# Jafar-SE_-_EasyEDA_-_Schematic_Export.net
KiCad netlist of a schematic drawn in EasyEDA
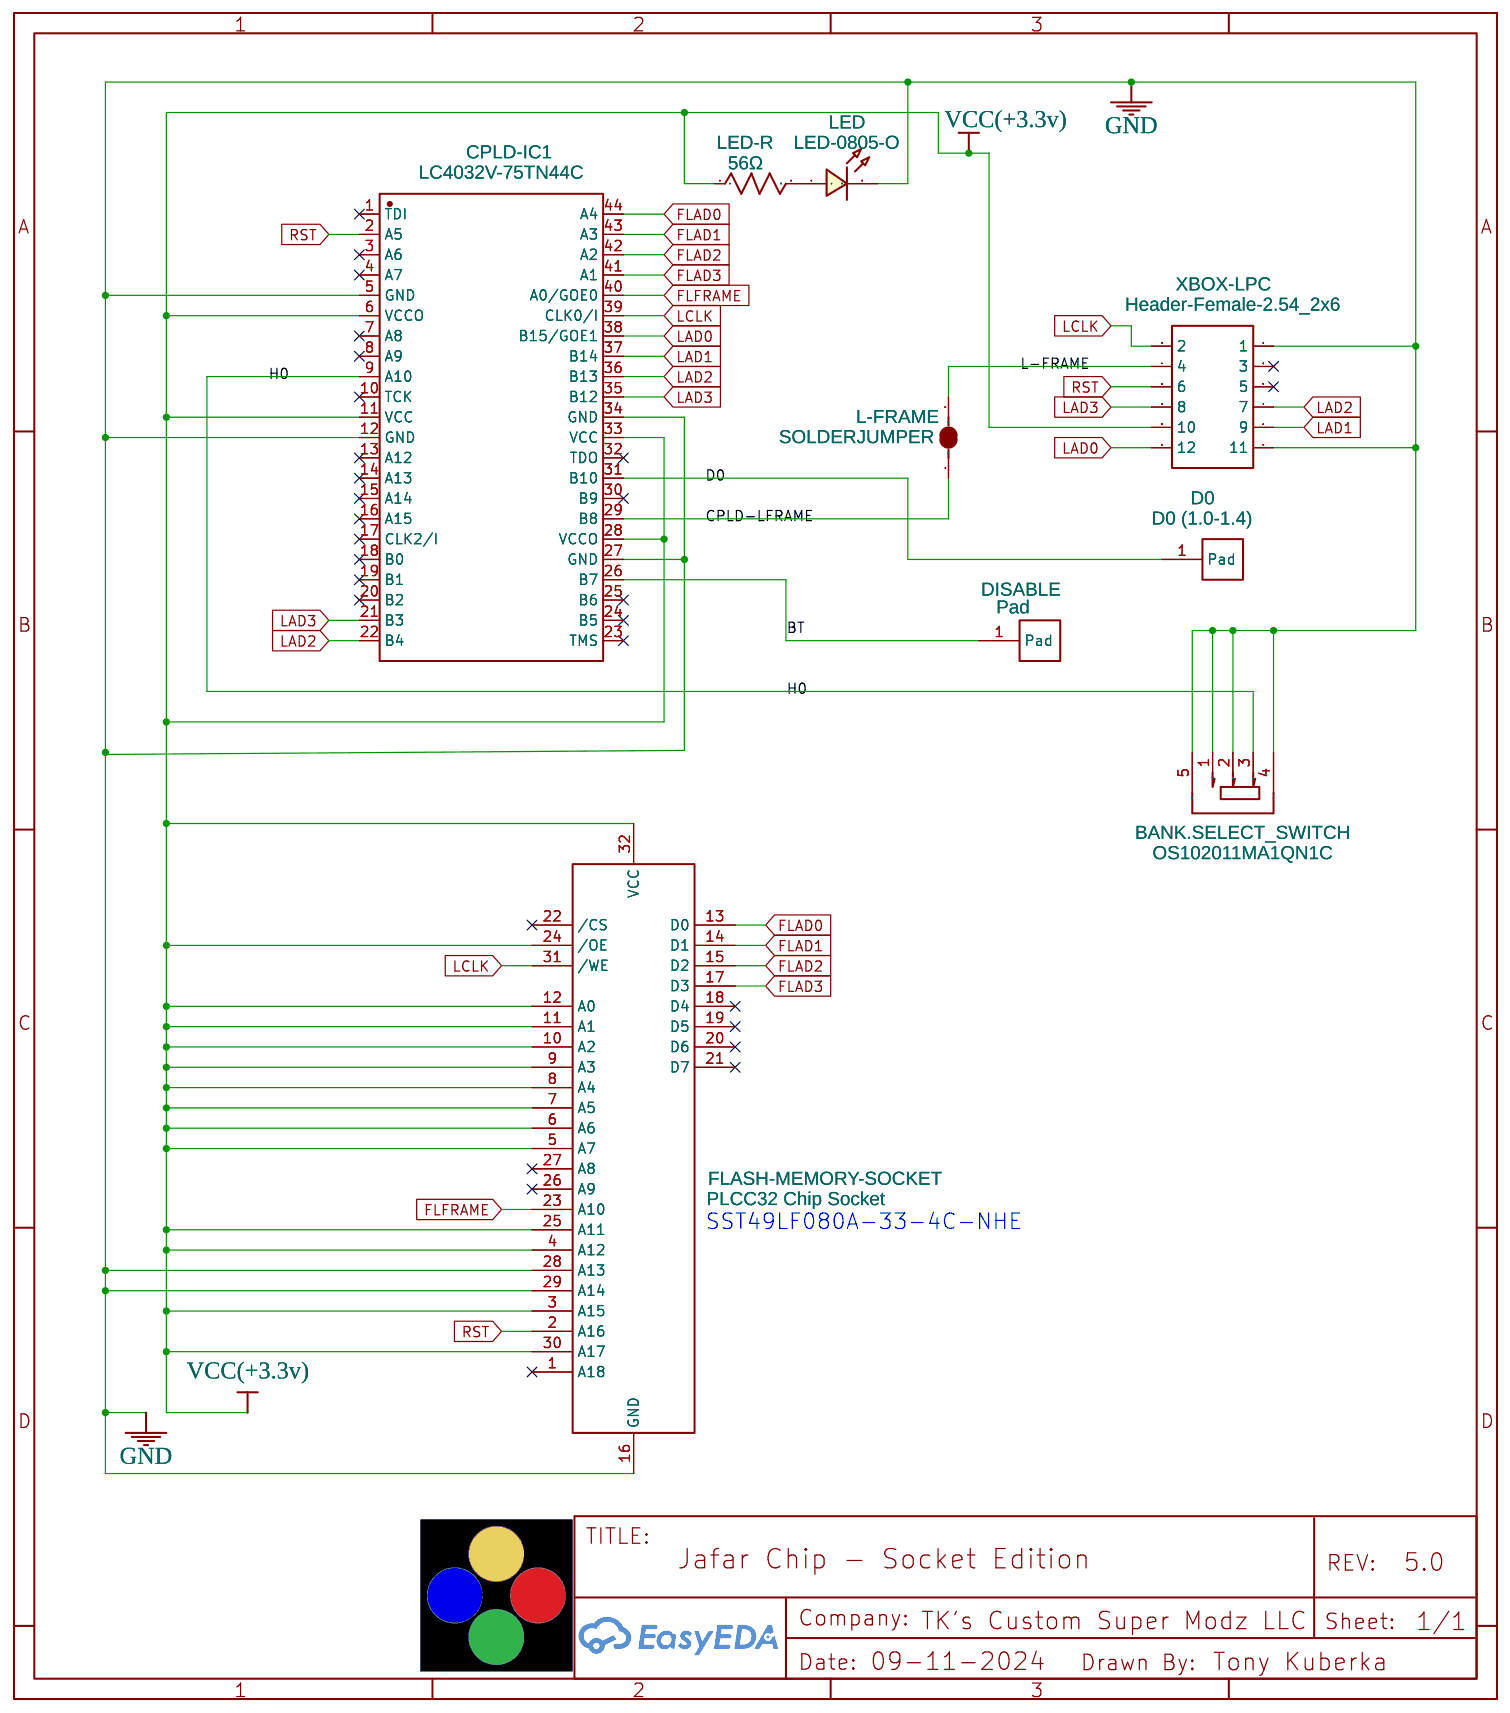
[diagram p0: schematic sheet]

(export (version "E")
  (design (tool "Eeschema 10.0.6"))
  (components
    (comp (ref "BANK.SELECT_SWITCH")
      (value "OS102011MA1QN1C")
      (fields (field (name "Manufacturer") "C&K"))
      (libsource (lib "") (part "OS102011MA1QN1C"))
    )
    (comp (ref "CPLD-IC1")
      (value "LC4032V-75TN44C")
      (fields (field (name "Manufacturer") "LATTICE(莱迪思)"))
      (libsource (lib "") (part "LC4032V-75TN44C"))
    )
    (comp (ref "D0") (value "D0 (1.0-1.4)") (libsource (lib "") (part "SOLDER PAD")))
    (comp (ref "DISABLE") (value "Pad") (libsource (lib "") (part "SOLDER PAD_1")))
    (comp (ref "FLASH-MEMORY-SOCKET")
      (value "PLCC32 Chip Socket")
      (fields
        (field (name "Manufacturer Part") "SST39VF040-70-4C-NHE")
        (field (name "Manufacturer") "Microchip Technology")
      )
      (libsource (lib "") (part "SST39VF040-70-4C-NHE"))
    )
    (comp (ref "L-FRAME") (value "SOLDERJUMPER") (libsource (lib "") (part "SOLDERJUMPER-OLDNC2")))
    (comp (ref "LED")
      (value "LED-0805-O")
      (fields
        (field (name "Manufacturer Part") "SZYY0805O")
        (field (name "Manufacturer") "Yongyu Photoelectric")
      )
      (libsource (lib "") (part "LED-0805-ORANGE"))
    )
    (comp (ref "LED-R") (value "56Ω") (libsource (lib "") (part "R_0805_US")))
    (comp (ref "XBOX-LPC")
      (value "Header-Female-2.54_2x6")
      (fields (field (name "Manufacturer Part") "2.54-2*6P母") (field (name "Manufacturer") "BOOMELE(博穆精密)"))
      (libsource (lib "") (part "Header-Female-2.54_2x6"))
    )
  )
  (nets
    (net (code "1") (name "/BT") (class "Default")
      (node (ref "CPLD-IC1") (pin "26") (pinfunction "B7_26") (pintype "unspecified"))
      (node (ref "DISABLE") (pin "1") (pinfunction "Pad_1") (pintype "unspecified"))
    )
    (net (code "2") (name "/CPLD-LFRAME") (class "Default")
      (node (ref "CPLD-IC1") (pin "29") (pinfunction "B8_29") (pintype "unspecified"))
      (node (ref "L-FRAME") (pin "1") (pinfunction "1_1") (pintype "unspecified"))
    )
    (net (code "3") (name "/D0") (class "Default")
      (node (ref "CPLD-IC1") (pin "31") (pinfunction "B10_31") (pintype "unspecified"))
      (node (ref "D0") (pin "1") (pinfunction "Pad_1") (pintype "unspecified"))
    )
    (net (code "4") (name "/H0") (class "Default")
      (node (ref "BANK.SELECT_SWITCH") (pin "3") (pinfunction "3_3") (pintype "unspecified"))
      (node (ref "CPLD-IC1") (pin "9") (pinfunction "A10_9") (pintype "unspecified"))
    )
    (net (code "5") (name "/L-FRAME") (class "Default")
      (node (ref "L-FRAME") (pin "2") (pinfunction "2_2") (pintype "unspecified"))
      (node (ref "XBOX-LPC") (pin "4") (pinfunction "4_4") (pintype "input"))
    )
    (net (code "6") (name "FLAD0") (class "Default")
      (node (ref "CPLD-IC1") (pin "44") (pinfunction "A4_44") (pintype "unspecified"))
      (node (ref "FLASH-MEMORY-SOCKET") (pin "13") (pinfunction "D0_13") (pintype "unspecified"))
    )
    (net (code "7") (name "FLAD1") (class "Default")
      (node (ref "CPLD-IC1") (pin "43") (pinfunction "A3_43") (pintype "unspecified"))
      (node (ref "FLASH-MEMORY-SOCKET") (pin "14") (pinfunction "D1_14") (pintype "unspecified"))
    )
    (net (code "8") (name "FLAD2") (class "Default")
      (node (ref "CPLD-IC1") (pin "42") (pinfunction "A2_42") (pintype "unspecified"))
      (node (ref "FLASH-MEMORY-SOCKET") (pin "15") (pinfunction "D2_15") (pintype "unspecified"))
    )
    (net (code "9") (name "FLAD3") (class "Default")
      (node (ref "CPLD-IC1") (pin "41") (pinfunction "A1_41") (pintype "unspecified"))
      (node (ref "FLASH-MEMORY-SOCKET") (pin "17") (pinfunction "D3_17") (pintype "unspecified"))
    )
    (net (code "10") (name "FLFRAME") (class "Default")
      (node (ref "CPLD-IC1") (pin "40") (pinfunction "A0/GOE0_40") (pintype "unspecified"))
      (node (ref "FLASH-MEMORY-SOCKET") (pin "23") (pinfunction "A10_23") (pintype "unspecified"))
    )
    (net (code "11") (name "GND") (class "Default")
      (node (ref "BANK.SELECT_SWITCH") (pin "1") (pinfunction "1_1") (pintype "unspecified"))
      (node (ref "BANK.SELECT_SWITCH") (pin "2") (pinfunction "2_2") (pintype "unspecified"))
      (node (ref "BANK.SELECT_SWITCH") (pin "4") (pinfunction "4_4") (pintype "unspecified"))
      (node (ref "BANK.SELECT_SWITCH") (pin "5") (pinfunction "5_5") (pintype "unspecified"))
      (node (ref "CPLD-IC1") (pin "12") (pinfunction "GND_12") (pintype "unspecified"))
      (node (ref "CPLD-IC1") (pin "27") (pinfunction "GND_27") (pintype "unspecified"))
      (node (ref "CPLD-IC1") (pin "34") (pinfunction "GND_34") (pintype "unspecified"))
      (node (ref "CPLD-IC1") (pin "5") (pinfunction "GND_5") (pintype "unspecified"))
      (node (ref "FLASH-MEMORY-SOCKET") (pin "16") (pinfunction "GND_16") (pintype "unspecified"))
      (node (ref "FLASH-MEMORY-SOCKET") (pin "28") (pinfunction "A13_28") (pintype "unspecified"))
      (node (ref "FLASH-MEMORY-SOCKET") (pin "29") (pinfunction "A14_29") (pintype "unspecified"))
      (node (ref "LED") (pin "2") (pinfunction "2_2") (pintype "unspecified"))
      (node (ref "XBOX-LPC") (pin "1") (pinfunction "1_1") (pintype "input"))
      (node (ref "XBOX-LPC") (pin "11") (pinfunction "11_11") (pintype "input"))
    )
    (net (code "12") (name "LAD0") (class "Default")
      (node (ref "CPLD-IC1") (pin "38") (pinfunction "B15/GOE1_38") (pintype "unspecified"))
      (node (ref "XBOX-LPC") (pin "12") (pinfunction "12_12") (pintype "input"))
    )
    (net (code "13") (name "LAD1") (class "Default")
      (node (ref "CPLD-IC1") (pin "37") (pinfunction "B14_37") (pintype "unspecified"))
      (node (ref "XBOX-LPC") (pin "9") (pinfunction "9_9") (pintype "input"))
    )
    (net (code "14") (name "LAD2") (class "Default")
      (node (ref "CPLD-IC1") (pin "22") (pinfunction "B4_22") (pintype "unspecified"))
      (node (ref "CPLD-IC1") (pin "36") (pinfunction "B13_36") (pintype "unspecified"))
      (node (ref "XBOX-LPC") (pin "7") (pinfunction "7_7") (pintype "input"))
    )
    (net (code "15") (name "LAD3") (class "Default")
      (node (ref "CPLD-IC1") (pin "21") (pinfunction "B3_21") (pintype "unspecified"))
      (node (ref "CPLD-IC1") (pin "35") (pinfunction "B12_35") (pintype "unspecified"))
      (node (ref "XBOX-LPC") (pin "8") (pinfunction "8_8") (pintype "input"))
    )
    (net (code "16") (name "LCLK") (class "Default")
      (node (ref "CPLD-IC1") (pin "39") (pinfunction "CLK0/I_39") (pintype "unspecified"))
      (node (ref "FLASH-MEMORY-SOCKET") (pin "31") (pinfunction "/WE_31") (pintype "unspecified"))
      (node (ref "XBOX-LPC") (pin "2") (pinfunction "2_2") (pintype "input"))
    )
    (net (code "17") (name "Net-(LED-Pad1)") (class "Default")
      (node (ref "LED") (pin "1") (pinfunction "1_1") (pintype "unspecified"))
      (node (ref "LED-R") (pin "2") (pinfunction "2_2") (pintype "unspecified"))
    )
    (net (code "18") (name "RST") (class "Default")
      (node (ref "CPLD-IC1") (pin "2") (pinfunction "A5_2") (pintype "unspecified"))
      (node (ref "FLASH-MEMORY-SOCKET") (pin "2") (pinfunction "A16_2") (pintype "unspecified"))
      (node (ref "XBOX-LPC") (pin "6") (pinfunction "6_6") (pintype "input"))
    )
    (net (code "19") (name "VCC(+3.3v)") (class "Default")
      (node (ref "CPLD-IC1") (pin "11") (pinfunction "VCC_11") (pintype "unspecified"))
      (node (ref "CPLD-IC1") (pin "28") (pinfunction "VCCO_28") (pintype "unspecified"))
      (node (ref "CPLD-IC1") (pin "33") (pinfunction "VCC_33") (pintype "unspecified"))
      (node (ref "CPLD-IC1") (pin "6") (pinfunction "VCCO_6") (pintype "unspecified"))
      (node (ref "FLASH-MEMORY-SOCKET") (pin "10") (pinfunction "A2_10") (pintype "unspecified"))
      (node (ref "FLASH-MEMORY-SOCKET") (pin "11") (pinfunction "A1_11") (pintype "unspecified"))
      (node (ref "FLASH-MEMORY-SOCKET") (pin "12") (pinfunction "A0_12") (pintype "unspecified"))
      (node (ref "FLASH-MEMORY-SOCKET") (pin "24") (pinfunction "/OE_24") (pintype "unspecified"))
      (node (ref "FLASH-MEMORY-SOCKET") (pin "25") (pinfunction "A11_25") (pintype "unspecified"))
      (node (ref "FLASH-MEMORY-SOCKET") (pin "3") (pinfunction "A15_3") (pintype "unspecified"))
      (node (ref "FLASH-MEMORY-SOCKET") (pin "30") (pinfunction "A17_30") (pintype "unspecified"))
      (node (ref "FLASH-MEMORY-SOCKET") (pin "32") (pinfunction "VCC_32") (pintype "unspecified"))
      (node (ref "FLASH-MEMORY-SOCKET") (pin "4") (pinfunction "A12_4") (pintype "unspecified"))
      (node (ref "FLASH-MEMORY-SOCKET") (pin "5") (pinfunction "A7_5") (pintype "unspecified"))
      (node (ref "FLASH-MEMORY-SOCKET") (pin "6") (pinfunction "A6_6") (pintype "unspecified"))
      (node (ref "FLASH-MEMORY-SOCKET") (pin "7") (pinfunction "A5_7") (pintype "unspecified"))
      (node (ref "FLASH-MEMORY-SOCKET") (pin "8") (pinfunction "A4_8") (pintype "unspecified"))
      (node (ref "FLASH-MEMORY-SOCKET") (pin "9") (pinfunction "A3_9") (pintype "unspecified"))
      (node (ref "LED-R") (pin "1") (pinfunction "1_1") (pintype "unspecified"))
      (node (ref "XBOX-LPC") (pin "10") (pinfunction "10_10") (pintype "input"))
    )
    (net (code "20") (name "unconnected-(CPLD-IC1-A6-Pad3)") (class "Default")
      (node (ref "CPLD-IC1") (pin "3") (pinfunction "A6_3") (pintype "unspecified+no_connect"))
    )
    (net (code "21") (name "unconnected-(CPLD-IC1-A7-Pad4)") (class "Default")
      (node (ref "CPLD-IC1") (pin "4") (pinfunction "A7_4") (pintype "unspecified+no_connect"))
    )
    (net (code "22") (name "unconnected-(CPLD-IC1-A8-Pad7)") (class "Default")
      (node (ref "CPLD-IC1") (pin "7") (pinfunction "A8_7") (pintype "unspecified+no_connect"))
    )
    (net (code "23") (name "unconnected-(CPLD-IC1-A9-Pad8)") (class "Default")
      (node (ref "CPLD-IC1") (pin "8") (pinfunction "A9_8") (pintype "unspecified+no_connect"))
    )
    (net (code "24") (name "unconnected-(CPLD-IC1-A12-Pad13)") (class "Default")
      (node (ref "CPLD-IC1") (pin "13") (pinfunction "A12_13") (pintype "unspecified+no_connect"))
    )
    (net (code "25") (name "unconnected-(CPLD-IC1-A13-Pad14)") (class "Default")
      (node (ref "CPLD-IC1") (pin "14") (pinfunction "A13_14") (pintype "unspecified+no_connect"))
    )
    (net (code "26") (name "unconnected-(CPLD-IC1-A14-Pad15)") (class "Default")
      (node (ref "CPLD-IC1") (pin "15") (pinfunction "A14_15") (pintype "unspecified+no_connect"))
    )
    (net (code "27") (name "unconnected-(CPLD-IC1-A15-Pad16)") (class "Default")
      (node (ref "CPLD-IC1") (pin "16") (pinfunction "A15_16") (pintype "unspecified+no_connect"))
    )
    (net (code "28") (name "unconnected-(CPLD-IC1-B0-Pad18)") (class "Default")
      (node (ref "CPLD-IC1") (pin "18") (pinfunction "B0_18") (pintype "unspecified+no_connect"))
    )
    (net (code "29") (name "unconnected-(CPLD-IC1-B1-Pad19)") (class "Default")
      (node (ref "CPLD-IC1") (pin "19") (pinfunction "B1_19") (pintype "unspecified+no_connect"))
    )
    (net (code "30") (name "unconnected-(CPLD-IC1-B2-Pad20)") (class "Default")
      (node (ref "CPLD-IC1") (pin "20") (pinfunction "B2_20") (pintype "unspecified+no_connect"))
    )
    (net (code "31") (name "unconnected-(CPLD-IC1-B5-Pad24)") (class "Default")
      (node (ref "CPLD-IC1") (pin "24") (pinfunction "B5_24") (pintype "unspecified+no_connect"))
    )
    (net (code "32") (name "unconnected-(CPLD-IC1-B6-Pad25)") (class "Default")
      (node (ref "CPLD-IC1") (pin "25") (pinfunction "B6_25") (pintype "unspecified+no_connect"))
    )
    (net (code "33") (name "unconnected-(CPLD-IC1-B9-Pad30)") (class "Default")
      (node (ref "CPLD-IC1") (pin "30") (pinfunction "B9_30") (pintype "unspecified+no_connect"))
    )
    (net (code "34") (name "unconnected-(CPLD-IC1-CLK2{slash}I-Pad17)") (class "Default")
      (node (ref "CPLD-IC1") (pin "17") (pinfunction "CLK2/I_17") (pintype "unspecified+no_connect"))
    )
    (net (code "35") (name "unconnected-(CPLD-IC1-TCK-Pad10)") (class "Default")
      (node (ref "CPLD-IC1") (pin "10") (pinfunction "TCK_10") (pintype "unspecified+no_connect"))
    )
    (net (code "36") (name "unconnected-(CPLD-IC1-TDI-Pad1)") (class "Default")
      (node (ref "CPLD-IC1") (pin "1") (pinfunction "TDI_1") (pintype "unspecified+no_connect"))
    )
    (net (code "37") (name "unconnected-(CPLD-IC1-TDO-Pad32)") (class "Default")
      (node (ref "CPLD-IC1") (pin "32") (pinfunction "TDO_32") (pintype "unspecified+no_connect"))
    )
    (net (code "38") (name "unconnected-(CPLD-IC1-TMS-Pad23)") (class "Default")
      (node (ref "CPLD-IC1") (pin "23") (pinfunction "TMS_23") (pintype "unspecified+no_connect"))
    )
    (net (code "39") (name "unconnected-(FLASH-MEMORY-SOCKET-A8-Pad27)") (class "Default")
      (node (ref "FLASH-MEMORY-SOCKET") (pin "27") (pinfunction "A8_27") (pintype "unspecified+no_connect"))
    )
    (net (code "40") (name "unconnected-(FLASH-MEMORY-SOCKET-A9-Pad26)") (class "Default")
      (node (ref "FLASH-MEMORY-SOCKET") (pin "26") (pinfunction "A9_26") (pintype "unspecified+no_connect"))
    )
    (net (code "41") (name "unconnected-(FLASH-MEMORY-SOCKET-A18-Pad1)") (class "Default")
      (node (ref "FLASH-MEMORY-SOCKET") (pin "1") (pinfunction "A18_1") (pintype "unspecified+no_connect"))
    )
    (net (code "42") (name "unconnected-(FLASH-MEMORY-SOCKET-D4-Pad18)") (class "Default")
      (node (ref "FLASH-MEMORY-SOCKET") (pin "18") (pinfunction "D4_18") (pintype "unspecified+no_connect"))
    )
    (net (code "43") (name "unconnected-(FLASH-MEMORY-SOCKET-D5-Pad19)") (class "Default")
      (node (ref "FLASH-MEMORY-SOCKET") (pin "19") (pinfunction "D5_19") (pintype "unspecified+no_connect"))
    )
    (net (code "44") (name "unconnected-(FLASH-MEMORY-SOCKET-D6-Pad20)") (class "Default")
      (node (ref "FLASH-MEMORY-SOCKET") (pin "20") (pinfunction "D6_20") (pintype "unspecified+no_connect"))
    )
    (net (code "45") (name "unconnected-(FLASH-MEMORY-SOCKET-D7-Pad21)") (class "Default")
      (node (ref "FLASH-MEMORY-SOCKET") (pin "21") (pinfunction "D7_21") (pintype "unspecified+no_connect"))
    )
    (net (code "46") (name "unconnected-(FLASH-MEMORY-SOCKET-{slash}CS-Pad22)") (class "Default")
      (node (ref "FLASH-MEMORY-SOCKET") (pin "22") (pinfunction "/CS_22") (pintype "unspecified+no_connect"))
    )
    (net (code "47") (name "unconnected-(XBOX-LPC-Pad3)") (class "Default")
      (node (ref "XBOX-LPC") (pin "3") (pinfunction "3_3") (pintype "input+no_connect"))
    )
    (net (code "48") (name "unconnected-(XBOX-LPC-Pad5)") (class "Default")
      (node (ref "XBOX-LPC") (pin "5") (pinfunction "5_5") (pintype "input+no_connect"))
    )
  )
)
